# EEM_CONN.net
KiCad netlist of a schematic drawn in Altium Designer
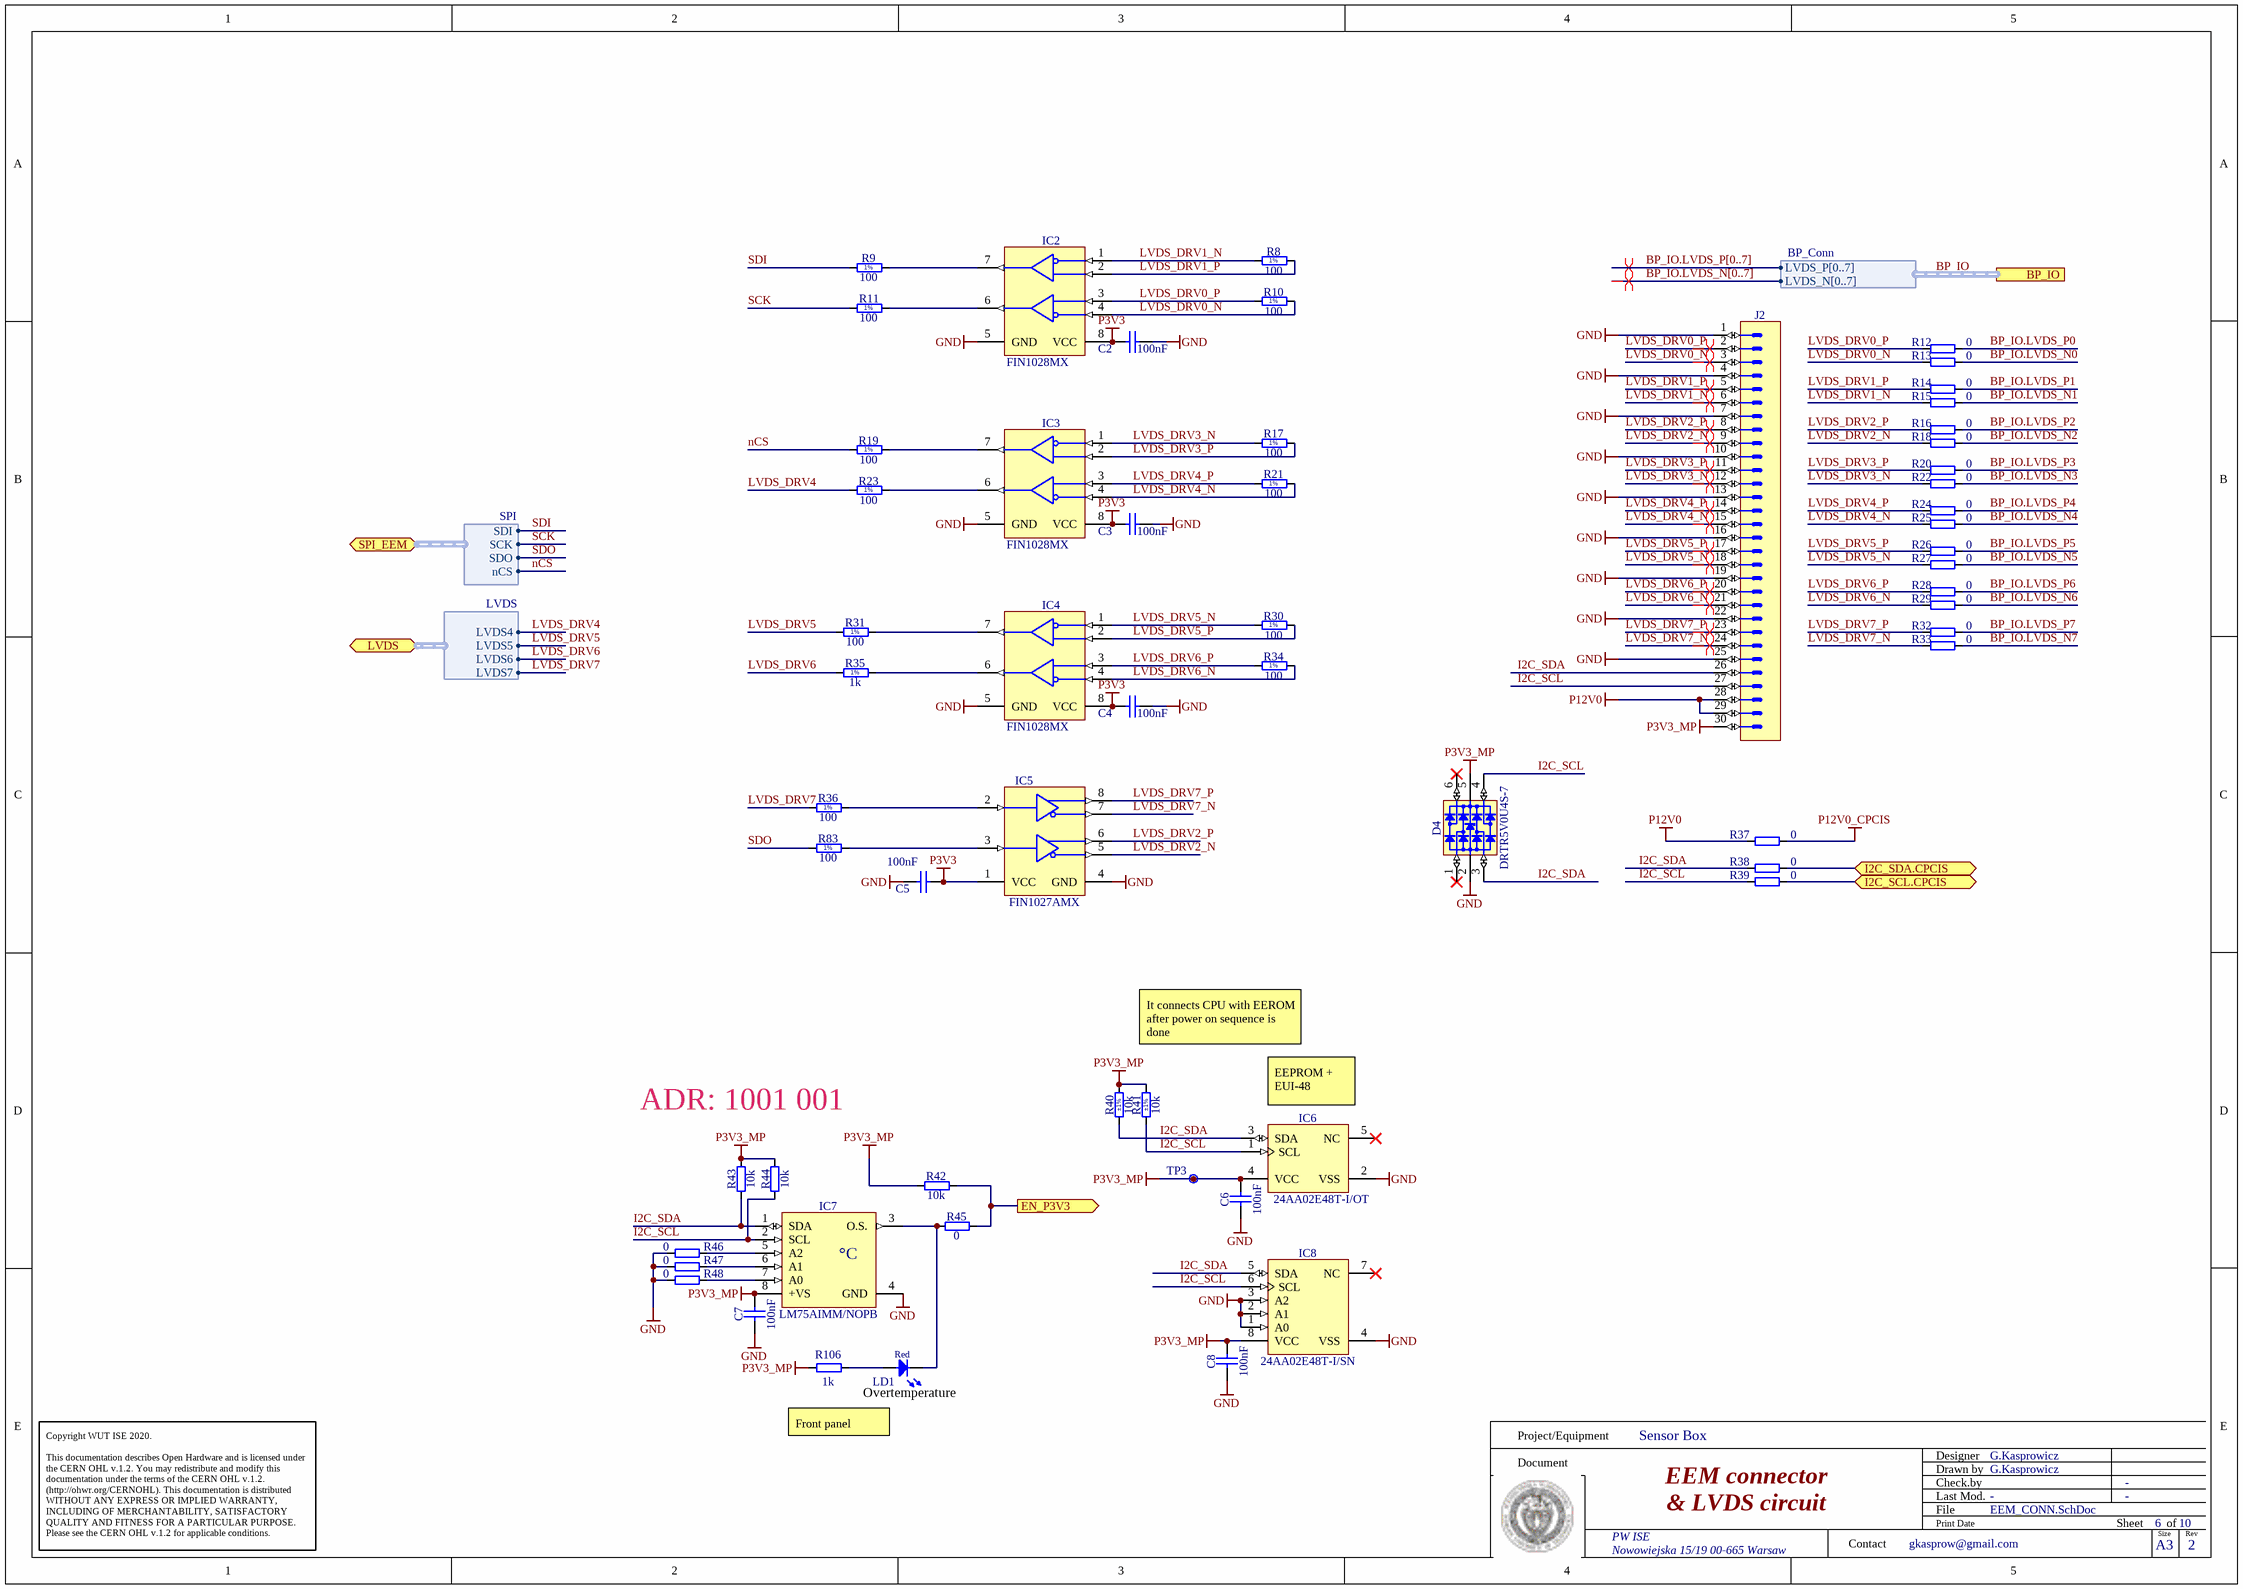
[diagram p0: EEM_CONN.SchDoc]

(export (version "E")
  (design (tool "Eeschema 10.0.6"))
  (components
    (comp (ref "C2")
      (value "100nF")
      (footprint "CAPC1005X55N")
      (description "Non-polarised capacitor")
      (fields
        (field (name "PART NUMBER") "CC0402_100NF_16V_10%_X5R")
        (field (name "VOLTAGE") "16V")
        (field (name "AUTHOR") "CERN DEM JLC")
      )
      (libsource (lib "Capacitors") (part "Capacitor - non polarized"))
    )
    (comp (ref "C3")
      (value "100nF")
      (footprint "CAPC1005X55N")
      (description "Non-polarised capacitor")
      (fields
        (field (name "PART NUMBER") "CC0402_100NF_16V_10%_X5R")
        (field (name "VOLTAGE") "16V")
        (field (name "AUTHOR") "CERN DEM JLC")
      )
      (libsource (lib "Capacitors") (part "Capacitor - non polarized"))
    )
    (comp (ref "C4")
      (value "100nF")
      (footprint "CAPC1005X55N")
      (description "Non-polarised capacitor")
      (fields
        (field (name "PART NUMBER") "CC0402_100NF_16V_10%_X5R")
        (field (name "VOLTAGE") "16V")
        (field (name "AUTHOR") "CERN DEM JLC")
      )
      (libsource (lib "Capacitors") (part "Capacitor - non polarized"))
    )
    (comp (ref "C5")
      (value "100nF")
      (footprint "CAPC1005X55N")
      (description "Non-polarised capacitor")
      (fields
        (field (name "PART NUMBER") "CC0402_100NF_16V_10%_X5R")
        (field (name "VOLTAGE") "16V")
        (field (name "AUTHOR") "CERN DEM JLC")
      )
      (libsource (lib "Capacitors") (part "Capacitor - non polarized"))
    )
    (comp (ref "C6")
      (value "100nF")
      (footprint "CAPC1005X55N")
      (description "Non-polarised capacitor")
      (fields
        (field (name "PART NUMBER") "CC0402_100NF_16V_10%_X5R")
        (field (name "VOLTAGE") "16V")
        (field (name "AUTHOR") "CERN DEM JLC")
      )
      (libsource (lib "Capacitors") (part "Capacitor - non polarized"))
    )
    (comp (ref "C7")
      (value "100nF")
      (footprint "CAPC1005X55N")
      (description "Non-polarised capacitor")
      (fields
        (field (name "PART NUMBER") "CC0402_100NF_16V_10%_X5R")
        (field (name "VOLTAGE") "16V")
        (field (name "AUTHOR") "CERN DEM JLC")
      )
      (libsource (lib "Capacitors") (part "Capacitor - non polarized"))
    )
    (comp (ref "C8")
      (value "100nF")
      (footprint "CAPC1005X55N")
      (description "Non-polarised capacitor")
      (fields
        (field (name "PART NUMBER") "CC0402_100NF_16V_10%_X5R")
        (field (name "VOLTAGE") "16V")
        (field (name "AUTHOR") "CERN DEM JLC")
      )
      (libsource (lib "Capacitors") (part "Capacitor - non polarized"))
    )
    (comp (ref "D4")
      (value "DRTR5V0U4S-7")
      (footprint "SOT65P210X110-6N")
      (description "Integrated Quad Ultra-Low Capacitance ESD Protection")
      (fields (field (name "MANUFACTURER") "DIODES") (field (name "AUTHOR") "GK"))
      (libsource (lib "Diodes") (part "D_TVS_DRTR5V0U4S-7"))
    )
    (comp (ref "IC2")
      (value "FIN1028MX")
      (footprint "SOIC127P600X175-8N")
      (description "3.3V LVDS 2-Bit High-Speed Differential Reciever")
      (fields (field (name "MANUFACTURER") "ON Semiconductor") (field (name "AUTHOR") "GK"))
      (libsource (lib "LIBRARY_SCH") (part "IFC_FIN1028"))
    )
    (comp (ref "IC3")
      (value "FIN1028MX")
      (footprint "SOIC127P600X175-8N")
      (description "3.3V LVDS 2-Bit High-Speed Differential Reciever")
      (fields (field (name "MANUFACTURER") "ON Semiconductor") (field (name "AUTHOR") "GK"))
      (libsource (lib "LIBRARY_SCH") (part "IFC_FIN1028"))
    )
    (comp (ref "IC4")
      (value "FIN1028MX")
      (footprint "SOIC127P600X175-8N")
      (description "3.3V LVDS 2-Bit High-Speed Differential Reciever")
      (fields (field (name "MANUFACTURER") "ON Semiconductor") (field (name "AUTHOR") "GK"))
      (libsource (lib "LIBRARY_SCH") (part "IFC_FIN1028"))
    )
    (comp (ref "IC5")
      (value "FIN1027AMX")
      (footprint "SOIC127P600X175-8N")
      (description "3.3V LVDS, 2-Bit, High-Speed, Differential Driver")
      (fields (field (name "MANUFACTURER") "ON Semiconductor") (field (name "AUTHOR") "GK"))
      (libsource (lib "LIBRARY_SCH") (part "IFC_FIN1027A"))
    )
    (comp (ref "IC6")
      (value "24AA02E48T-I/OT")
      (footprint "SOT95P280X145-5N")
      (description "1.7V-5.5V, 2K I2C Serial EEPROM With EUI-48 Node Identity")
      (fields (field (name "MANUFACTURER") "MICROCHIP TECHNOLOGY") (field (name "AUTHOR") "CERN DEM MR"))
      (libsource (lib "ICs And Semiconductors") (part "24AA02E48T-I/OT"))
    )
    (comp (ref "IC7")
      (value "LM75AIMM/NOPB")
      (footprint "SOP65P490X109-8N")
      (description "Digital Temperature Sensor and Thermal Watchdog with Two-Wire Interface")
      (fields (field (name "MANUFACTURER") "TEXAS INSTRUMENTS") (field (name "AUTHOR") "CERN DEM JLC"))
      (libsource (lib "ICs And Semiconductors") (part "LM75"))
    )
    (comp (ref "IC8")
      (value "24AA02E48T-I/SN")
      (footprint "SOIC127P600X175-8N")
      (description "1.7V-5.5V, 2K I2C™ Serial EEPROMs with EUI-48™ Node Identity")
      (fields (field (name "MANUFACTURER") "MICROCHIP TECHNOLOGY") (field (name "AUTHOR") "CERN DEM MR"))
      (libsource (lib "ICs And Semiconductors") (part "24AA025E48-I/SN"))
    )
    (comp (ref "J2")
      (value "IDC")
      (footprint "3M_N2530-6002RB")
      (description "Connector 30 Male")
      (fields
        (field (name "PART NUMBER") "3M_N2530-6002RB")
        (field (name "MANUFACTURER") "3M")
        (field (name "AUTHOR") "CERN DEM JLC")
      )
      (libsource (lib "Connectors") (part "Connector 30 Male"))
    )
    (comp (ref "LD1")
      (value "Red")
      (footprint "LED_DIALIGHT_555-200")
      (description "LED Red 1C 2A")
      (fields
        (field (name "PART NUMBER") "LED_DIALIGHT_555-2001F")
        (field (name "MANUFACTURER") "DIALIGHT")
        (field (name "AUTHOR") "CERN DEM JMW")
      )
      (libsource (lib "ICs And Semiconductors") (part "LED Red 1C 2A"))
    )
    (comp (ref "R8")
      (value "100")
      (footprint "RESC1005X40N")
      (description "Resistor - 1%")
      (fields
        (field (name "PART NUMBER") "R0402_100R_1%_0.0625W_100PPM")
        (field (name "POWER") "0.0625W")
        (field (name "AUTHOR") "CERN DEM JLC")
      )
      (libsource (lib "Resistors") (part "Resistor - 1%"))
    )
    (comp (ref "R9")
      (value "100")
      (footprint "RESC1005X40N")
      (description "Resistor - 1%")
      (fields
        (field (name "PART NUMBER") "R0402_100R_1%_0.0625W_100PPM")
        (field (name "POWER") "0.0625W")
        (field (name "AUTHOR") "CERN DEM JLC")
      )
      (libsource (lib "Resistors") (part "Resistor - 1%"))
    )
    (comp (ref "R10")
      (value "100")
      (footprint "RESC1005X40N")
      (description "Resistor - 1%")
      (fields
        (field (name "PART NUMBER") "R0402_100R_1%_0.0625W_100PPM")
        (field (name "POWER") "0.0625W")
        (field (name "AUTHOR") "CERN DEM JLC")
      )
      (libsource (lib "Resistors") (part "Resistor - 1%"))
    )
    (comp (ref "R11")
      (value "100")
      (footprint "RESC1005X40N")
      (description "Resistor - 1%")
      (fields
        (field (name "PART NUMBER") "R0402_100R_1%_0.0625W_100PPM")
        (field (name "POWER") "0.0625W")
        (field (name "AUTHOR") "CERN DEM JLC")
      )
      (libsource (lib "Resistors") (part "Resistor - 1%"))
    )
    (comp (ref "R12")
      (value "0")
      (footprint "RESC1005X40N")
      (description "Resistor")
      (fields
        (field (name "PART NUMBER") "R0402_0R_JUMPER")
        (field (name "MANUFACTURER") "GENERIC")
        (field (name "AUTHOR") "CERN DEM JLC")
      )
      (libsource (lib "Resistors") (part "Resistor"))
    )
    (comp (ref "R13")
      (value "0")
      (footprint "RESC1005X40N")
      (description "Resistor")
      (fields
        (field (name "PART NUMBER") "R0402_0R_JUMPER")
        (field (name "MANUFACTURER") "GENERIC")
        (field (name "AUTHOR") "CERN DEM JLC")
      )
      (libsource (lib "Resistors") (part "Resistor"))
    )
    (comp (ref "R14")
      (value "0")
      (footprint "RESC1005X40N")
      (description "Resistor")
      (fields
        (field (name "PART NUMBER") "R0402_0R_JUMPER")
        (field (name "MANUFACTURER") "GENERIC")
        (field (name "AUTHOR") "CERN DEM JLC")
      )
      (libsource (lib "Resistors") (part "Resistor"))
    )
    (comp (ref "R15")
      (value "0")
      (footprint "RESC1005X40N")
      (description "Resistor")
      (fields
        (field (name "PART NUMBER") "R0402_0R_JUMPER")
        (field (name "MANUFACTURER") "GENERIC")
        (field (name "AUTHOR") "CERN DEM JLC")
      )
      (libsource (lib "Resistors") (part "Resistor"))
    )
    (comp (ref "R16")
      (value "0")
      (footprint "RESC1005X40N")
      (description "Resistor")
      (fields
        (field (name "PART NUMBER") "R0402_0R_JUMPER")
        (field (name "MANUFACTURER") "GENERIC")
        (field (name "AUTHOR") "CERN DEM JLC")
      )
      (libsource (lib "Resistors") (part "Resistor"))
    )
    (comp (ref "R17")
      (value "100")
      (footprint "RESC1005X40N")
      (description "Resistor - 1%")
      (fields
        (field (name "PART NUMBER") "R0402_100R_1%_0.0625W_100PPM")
        (field (name "POWER") "0.0625W")
        (field (name "AUTHOR") "CERN DEM JLC")
      )
      (libsource (lib "Resistors") (part "Resistor - 1%"))
    )
    (comp (ref "R18")
      (value "0")
      (footprint "RESC1005X40N")
      (description "Resistor")
      (fields
        (field (name "PART NUMBER") "R0402_0R_JUMPER")
        (field (name "MANUFACTURER") "GENERIC")
        (field (name "AUTHOR") "CERN DEM JLC")
      )
      (libsource (lib "Resistors") (part "Resistor"))
    )
    (comp (ref "R19")
      (value "100")
      (footprint "RESC1005X40N")
      (description "Resistor - 1%")
      (fields
        (field (name "PART NUMBER") "R0402_100R_1%_0.0625W_100PPM")
        (field (name "POWER") "0.0625W")
        (field (name "AUTHOR") "CERN DEM JLC")
      )
      (libsource (lib "Resistors") (part "Resistor - 1%"))
    )
    (comp (ref "R20")
      (value "0")
      (footprint "RESC1005X40N")
      (description "Resistor")
      (fields
        (field (name "PART NUMBER") "R0402_0R_JUMPER")
        (field (name "MANUFACTURER") "GENERIC")
        (field (name "AUTHOR") "CERN DEM JLC")
      )
      (libsource (lib "Resistors") (part "Resistor"))
    )
    (comp (ref "R21")
      (value "100")
      (footprint "RESC1005X40N")
      (description "Resistor - 1%")
      (fields
        (field (name "PART NUMBER") "R0402_100R_1%_0.0625W_100PPM")
        (field (name "POWER") "0.0625W")
        (field (name "AUTHOR") "CERN DEM JLC")
      )
      (libsource (lib "Resistors") (part "Resistor - 1%"))
    )
    (comp (ref "R22")
      (value "0")
      (footprint "RESC1005X40N")
      (description "Resistor")
      (fields
        (field (name "PART NUMBER") "R0402_0R_JUMPER")
        (field (name "MANUFACTURER") "GENERIC")
        (field (name "AUTHOR") "CERN DEM JLC")
      )
      (libsource (lib "Resistors") (part "Resistor"))
    )
    (comp (ref "R23")
      (value "100")
      (footprint "RESC1005X40N")
      (description "Resistor - 1%")
      (fields
        (field (name "PART NUMBER") "R0402_100R_1%_0.0625W_100PPM")
        (field (name "POWER") "0.0625W")
        (field (name "AUTHOR") "CERN DEM JLC")
      )
      (libsource (lib "Resistors") (part "Resistor - 1%"))
    )
    (comp (ref "R24")
      (value "0")
      (footprint "RESC1005X40N")
      (description "Resistor")
      (fields
        (field (name "PART NUMBER") "R0402_0R_JUMPER")
        (field (name "MANUFACTURER") "GENERIC")
        (field (name "AUTHOR") "CERN DEM JLC")
      )
      (libsource (lib "Resistors") (part "Resistor"))
    )
    (comp (ref "R25")
      (value "0")
      (footprint "RESC1005X40N")
      (description "Resistor")
      (fields
        (field (name "PART NUMBER") "R0402_0R_JUMPER")
        (field (name "MANUFACTURER") "GENERIC")
        (field (name "AUTHOR") "CERN DEM JLC")
      )
      (libsource (lib "Resistors") (part "Resistor"))
    )
    (comp (ref "R26")
      (value "0")
      (footprint "RESC1005X40N")
      (description "Resistor")
      (fields
        (field (name "PART NUMBER") "R0402_0R_JUMPER")
        (field (name "MANUFACTURER") "GENERIC")
        (field (name "AUTHOR") "CERN DEM JLC")
      )
      (libsource (lib "Resistors") (part "Resistor"))
    )
    (comp (ref "R27")
      (value "0")
      (footprint "RESC1005X40N")
      (description "Resistor")
      (fields
        (field (name "PART NUMBER") "R0402_0R_JUMPER")
        (field (name "MANUFACTURER") "GENERIC")
        (field (name "AUTHOR") "CERN DEM JLC")
      )
      (libsource (lib "Resistors") (part "Resistor"))
    )
    (comp (ref "R28")
      (value "0")
      (footprint "RESC1005X40N")
      (description "Resistor")
      (fields
        (field (name "PART NUMBER") "R0402_0R_JUMPER")
        (field (name "MANUFACTURER") "GENERIC")
        (field (name "AUTHOR") "CERN DEM JLC")
      )
      (libsource (lib "Resistors") (part "Resistor"))
    )
    (comp (ref "R29")
      (value "0")
      (footprint "RESC1005X40N")
      (description "Resistor")
      (fields
        (field (name "PART NUMBER") "R0402_0R_JUMPER")
        (field (name "MANUFACTURER") "GENERIC")
        (field (name "AUTHOR") "CERN DEM JLC")
      )
      (libsource (lib "Resistors") (part "Resistor"))
    )
    (comp (ref "R30")
      (value "100")
      (footprint "RESC1005X40N")
      (description "Resistor - 1%")
      (fields
        (field (name "PART NUMBER") "R0402_100R_1%_0.0625W_100PPM")
        (field (name "POWER") "0.0625W")
        (field (name "AUTHOR") "CERN DEM JLC")
      )
      (libsource (lib "Resistors") (part "Resistor - 1%"))
    )
    (comp (ref "R31")
      (value "100")
      (footprint "RESC1005X40N")
      (description "Resistor - 1%")
      (fields
        (field (name "PART NUMBER") "R0402_100R_1%_0.0625W_100PPM")
        (field (name "POWER") "0.0625W")
        (field (name "AUTHOR") "CERN DEM JLC")
      )
      (libsource (lib "Resistors") (part "Resistor - 1%"))
    )
    (comp (ref "R32")
      (value "0")
      (footprint "RESC1005X40N")
      (description "Resistor")
      (fields
        (field (name "PART NUMBER") "R0402_0R_JUMPER")
        (field (name "MANUFACTURER") "GENERIC")
        (field (name "AUTHOR") "CERN DEM JLC")
      )
      (libsource (lib "Resistors") (part "Resistor"))
    )
    (comp (ref "R33")
      (value "0")
      (footprint "RESC1005X40N")
      (description "Resistor")
      (fields
        (field (name "PART NUMBER") "R0402_0R_JUMPER")
        (field (name "MANUFACTURER") "GENERIC")
        (field (name "AUTHOR") "CERN DEM JLC")
      )
      (libsource (lib "Resistors") (part "Resistor"))
    )
    (comp (ref "R34")
      (value "100")
      (footprint "RESC1005X40N")
      (description "Resistor - 1%")
      (fields
        (field (name "PART NUMBER") "R0402_100R_1%_0.0625W_100PPM")
        (field (name "POWER") "0.0625W")
        (field (name "AUTHOR") "CERN DEM JLC")
      )
      (libsource (lib "Resistors") (part "Resistor - 1%"))
    )
    (comp (ref "R35")
      (value "1k")
      (footprint "RESC1005X40N")
      (description "Resistor - 1%")
      (fields
        (field (name "PART NUMBER") "R0402_1K_1%_0.0625W_100PPM")
        (field (name "POWER") "0.0625W")
        (field (name "AUTHOR") "CERN DEM JLC")
      )
      (libsource (lib "Resistors") (part "Resistor - 1%"))
    )
    (comp (ref "R36")
      (value "100")
      (footprint "RESC1005X40N")
      (description "Resistor - 1%")
      (fields
        (field (name "PART NUMBER") "R0402_100R_1%_0.0625W_100PPM")
        (field (name "POWER") "0.0625W")
        (field (name "AUTHOR") "CERN DEM JLC")
      )
      (libsource (lib "Resistors") (part "Resistor - 1%"))
    )
    (comp (ref "R37")
      (value "0")
      (footprint "RESC2012X60N")
      (description "Resistor")
      (fields
        (field (name "PART NUMBER") "R0805_0R_JUMPER")
        (field (name "MANUFACTURER") "GENERIC")
        (field (name "AUTHOR") "CERN DEM JLC")
      )
      (libsource (lib "Resistors") (part "Resistor"))
    )
    (comp (ref "R38")
      (value "0")
      (footprint "RESC1005X40N")
      (description "Resistor")
      (fields
        (field (name "PART NUMBER") "R0402_0R_JUMPER")
        (field (name "MANUFACTURER") "GENERIC")
        (field (name "AUTHOR") "CERN DEM JLC")
      )
      (libsource (lib "Resistors") (part "Resistor"))
    )
    (comp (ref "R39")
      (value "0")
      (footprint "RESC1005X40N")
      (description "Resistor")
      (fields
        (field (name "PART NUMBER") "R0402_0R_JUMPER")
        (field (name "MANUFACTURER") "GENERIC")
        (field (name "AUTHOR") "CERN DEM JLC")
      )
      (libsource (lib "Resistors") (part "Resistor"))
    )
    (comp (ref "R40")
      (value "10k")
      (footprint "RESC1005X40N")
      (description "Resistor - 1%")
      (fields
        (field (name "TOLERANCE") "±1%")
        (field (name "PART NUMBER") "R0402_10K_1%_0.0625W_100PPM")
        (field (name "POWER") "0.0625W")
        (field (name "AUTHOR") "CERN DEM JLC")
      )
      (libsource (lib "Resistors") (part "Resistor - 1%"))
    )
    (comp (ref "R41")
      (value "10k")
      (footprint "RESC1005X40N")
      (description "Resistor - 1%")
      (fields
        (field (name "TOLERANCE") "±1%")
        (field (name "PART NUMBER") "R0402_10K_1%_0.0625W_100PPM")
        (field (name "POWER") "0.0625W")
        (field (name "AUTHOR") "CERN DEM JLC")
      )
      (libsource (lib "Resistors") (part "Resistor - 1%"))
    )
    (comp (ref "R42")
      (value "10k")
      (footprint "RESC1005X40N")
      (description "Resistor - 1%")
      (fields
        (field (name "PART NUMBER") "R0402_10K_1%_0.0625W_100PPM")
        (field (name "POWER") "0.0625W")
        (field (name "AUTHOR") "CERN DEM JLC")
      )
      (libsource (lib "Resistors") (part "Resistor - 1%"))
    )
    (comp (ref "R43")
      (value "10k")
      (footprint "RESC1005X40N")
      (description "Resistor - 1%")
      (fields
        (field (name "PART NUMBER") "R0402_10K_1%_0.0625W_100PPM")
        (field (name "POWER") "0.0625W")
        (field (name "AUTHOR") "CERN DEM JLC")
      )
      (libsource (lib "Resistors") (part "Resistor - 1%"))
    )
    (comp (ref "R44")
      (value "10k")
      (footprint "RESC1005X40N")
      (description "Resistor - 1%")
      (fields
        (field (name "PART NUMBER") "R0402_10K_1%_0.0625W_100PPM")
        (field (name "POWER") "0.0625W")
        (field (name "AUTHOR") "CERN DEM JLC")
      )
      (libsource (lib "Resistors") (part "Resistor - 1%"))
    )
    (comp (ref "R45")
      (value "0")
      (footprint "RESC1005X40N")
      (description "Resistor")
      (fields
        (field (name "PART NUMBER") "R0402_0R_JUMPER")
        (field (name "MANUFACTURER") "GENERIC")
        (field (name "AUTHOR") "CERN DEM JLC")
      )
      (libsource (lib "Resistors") (part "Resistor"))
    )
    (comp (ref "R46")
      (value "0")
      (footprint "RESC1005X40N")
      (description "Resistor")
      (fields
        (field (name "PART NUMBER") "R0402_0R_JUMPER")
        (field (name "MANUFACTURER") "GENERIC")
        (field (name "AUTHOR") "CERN DEM JLC")
      )
      (libsource (lib "Resistors") (part "Resistor"))
    )
    (comp (ref "R47")
      (value "0")
      (footprint "RESC1005X40N")
      (description "Resistor")
      (fields
        (field (name "PART NUMBER") "R0402_0R_JUMPER")
        (field (name "MANUFACTURER") "GENERIC")
        (field (name "AUTHOR") "CERN DEM JLC")
      )
      (libsource (lib "Resistors") (part "Resistor"))
    )
    (comp (ref "R48")
      (value "0")
      (footprint "RESC1005X40N")
      (description "Resistor")
      (fields
        (field (name "PART NUMBER") "R0402_0R_JUMPER")
        (field (name "MANUFACTURER") "GENERIC")
        (field (name "AUTHOR") "CERN DEM JLC")
      )
      (libsource (lib "Resistors") (part "Resistor"))
    )
    (comp (ref "R83")
      (value "100")
      (footprint "RESC1005X40N")
      (description "Resistor - 1%")
      (fields
        (field (name "PART NUMBER") "R0402_100R_1%_0.0625W_100PPM")
        (field (name "POWER") "0.0625W")
        (field (name "AUTHOR") "CERN DEM JLC")
      )
      (libsource (lib "Resistors") (part "Resistor - 1%"))
    )
    (comp (ref "R106")
      (value "1k")
      (footprint "RESC1005X40N")
      (description "Resistor - 1%")
      (fields
        (field (name "PART NUMBER") "R0402_1K_1%_0.0625W_100PPM")
        (field (name "POWER") "0.0625W")
        (field (name "AUTHOR") "CERN DEM JLC")
      )
      (libsource (lib "Resistors") (part "Resistor - 1%"))
    )
    (comp (ref "TP3")
      (value "Test Point")
      (footprint "TPS127")
      (fields (field (name "PART NUMBER") "SMD_PAD_1.27X1.27MM") (field (name "AUTHOR") "CERN DEM JLC"))
      (libsource (lib "Eletro-mechanical") (part "Test Point"))
    )
  )
  (nets
    (net (code "4") (name "/BP_IO.LVDS_N0") (class "Default")
      (node (ref "R13") (pin "2") (pinfunction "2_2") (pintype "passive"))
    )
    (net (code "5") (name "/BP_IO.LVDS_N1") (class "Default")
      (node (ref "R15") (pin "2") (pinfunction "2_2") (pintype "passive"))
    )
    (net (code "6") (name "/BP_IO.LVDS_N2") (class "Default")
      (node (ref "R18") (pin "2") (pinfunction "2_2") (pintype "passive"))
    )
    (net (code "7") (name "/BP_IO.LVDS_N3") (class "Default")
      (node (ref "R22") (pin "2") (pinfunction "2_2") (pintype "passive"))
    )
    (net (code "8") (name "/BP_IO.LVDS_N4") (class "Default")
      (node (ref "R25") (pin "2") (pinfunction "2_2") (pintype "passive"))
    )
    (net (code "9") (name "/BP_IO.LVDS_N5") (class "Default")
      (node (ref "R27") (pin "2") (pinfunction "2_2") (pintype "passive"))
    )
    (net (code "10") (name "/BP_IO.LVDS_N6") (class "Default")
      (node (ref "R29") (pin "2") (pinfunction "2_2") (pintype "passive"))
    )
    (net (code "11") (name "/BP_IO.LVDS_N7") (class "Default")
      (node (ref "R33") (pin "2") (pinfunction "2_2") (pintype "passive"))
    )
    (net (code "13") (name "/BP_IO.LVDS_P0") (class "Default")
      (node (ref "R12") (pin "2") (pinfunction "2_2") (pintype "passive"))
    )
    (net (code "14") (name "/BP_IO.LVDS_P1") (class "Default")
      (node (ref "R14") (pin "2") (pinfunction "2_2") (pintype "passive"))
    )
    (net (code "15") (name "/BP_IO.LVDS_P2") (class "Default")
      (node (ref "R16") (pin "2") (pinfunction "2_2") (pintype "passive"))
    )
    (net (code "16") (name "/BP_IO.LVDS_P3") (class "Default")
      (node (ref "R20") (pin "2") (pinfunction "2_2") (pintype "passive"))
    )
    (net (code "17") (name "/BP_IO.LVDS_P4") (class "Default")
      (node (ref "R24") (pin "2") (pinfunction "2_2") (pintype "passive"))
    )
    (net (code "18") (name "/BP_IO.LVDS_P5") (class "Default")
      (node (ref "R26") (pin "2") (pinfunction "2_2") (pintype "passive"))
    )
    (net (code "19") (name "/BP_IO.LVDS_P6") (class "Default")
      (node (ref "R28") (pin "2") (pinfunction "2_2") (pintype "passive"))
    )
    (net (code "20") (name "/BP_IO.LVDS_P7") (class "Default")
      (node (ref "R32") (pin "2") (pinfunction "2_2") (pintype "passive"))
    )
    (net (code "23") (name "/EN_P3V3") (class "Default")
      (node (ref "R42") (pin "2") (pinfunction "2_2") (pintype "passive"))
      (node (ref "R45") (pin "2") (pinfunction "2_2") (pintype "passive"))
    )
    (net (code "24") (name "/I2C_SCL") (class "Default")
      (node (ref "D4") (pin "4") (pinfunction "I/O3_4") (pintype "bidirectional"))
      (node (ref "IC6") (pin "1") (pinfunction "SCL_1") (pintype "input"))
      (node (ref "IC7") (pin "2") (pinfunction "SCL_2") (pintype "input"))
      (node (ref "IC8") (pin "6") (pinfunction "SCL_6") (pintype "input"))
      (node (ref "J2") (pin "27") (pinfunction "27_27") (pintype "bidirectional"))
      (node (ref "R39") (pin "1") (pinfunction "1_1") (pintype "passive"))
      (node (ref "R41") (pin "1") (pinfunction "1_1") (pintype "passive"))
      (node (ref "R44") (pin "1") (pinfunction "1_1") (pintype "passive"))
    )
    (net (code "25") (name "/I2C_SCL.CPCIS") (class "Default")
      (node (ref "R39") (pin "2") (pinfunction "2_2") (pintype "passive"))
    )
    (net (code "26") (name "/I2C_SDA") (class "Default")
      (node (ref "D4") (pin "3") (pinfunction "I/O2_3") (pintype "bidirectional"))
      (node (ref "IC6") (pin "3") (pinfunction "SDA_3") (pintype "bidirectional"))
      (node (ref "IC7") (pin "1") (pinfunction "SDA_1") (pintype "bidirectional"))
      (node (ref "IC8") (pin "5") (pinfunction "SDA_5") (pintype "bidirectional"))
      (node (ref "J2") (pin "26") (pinfunction "26_26") (pintype "bidirectional"))
      (node (ref "R38") (pin "1") (pinfunction "1_1") (pintype "passive"))
      (node (ref "R40") (pin "1") (pinfunction "1_1") (pintype "passive"))
      (node (ref "R43") (pin "1") (pinfunction "1_1") (pintype "passive"))
    )
    (net (code "27") (name "/I2C_SDA.CPCIS") (class "Default")
      (node (ref "R38") (pin "2") (pinfunction "2_2") (pintype "passive"))
    )
    (net (code "28") (name "/LVDS_DRV0_N") (class "Default")
      (node (ref "IC2") (pin "4") (pinfunction "RIN2-_4") (pintype "input"))
      (node (ref "J2") (pin "3") (pinfunction "3_3") (pintype "bidirectional"))
      (node (ref "R10") (pin "2") (pinfunction "2_2") (pintype "passive"))
      (node (ref "R13") (pin "1") (pinfunction "1_1") (pintype "passive"))
    )
    (net (code "29") (name "/LVDS_DRV0_P") (class "Default")
      (node (ref "IC2") (pin "3") (pinfunction "RIN2+_3") (pintype "input"))
      (node (ref "J2") (pin "2") (pinfunction "2_2") (pintype "bidirectional"))
      (node (ref "R10") (pin "1") (pinfunction "1_1") (pintype "passive"))
      (node (ref "R12") (pin "1") (pinfunction "1_1") (pintype "passive"))
    )
    (net (code "30") (name "/LVDS_DRV1_N") (class "Default")
      (node (ref "IC2") (pin "1") (pinfunction "RIN1-_1") (pintype "input"))
      (node (ref "J2") (pin "6") (pinfunction "6_6") (pintype "bidirectional"))
      (node (ref "R15") (pin "1") (pinfunction "1_1") (pintype "passive"))
      (node (ref "R8") (pin "1") (pinfunction "1_1") (pintype "passive"))
    )
    (net (code "31") (name "/LVDS_DRV1_P") (class "Default")
      (node (ref "IC2") (pin "2") (pinfunction "RIN1+_2") (pintype "input"))
      (node (ref "J2") (pin "5") (pinfunction "5_5") (pintype "bidirectional"))
      (node (ref "R14") (pin "1") (pinfunction "1_1") (pintype "passive"))
      (node (ref "R8") (pin "2") (pinfunction "2_2") (pintype "passive"))
    )
    (net (code "32") (name "/LVDS_DRV2_N") (class "Default")
      (node (ref "IC5") (pin "5") (pinfunction "DOUT-_5") (pintype "output"))
      (node (ref "J2") (pin "9") (pinfunction "9_9") (pintype "bidirectional"))
      (node (ref "R18") (pin "1") (pinfunction "1_1") (pintype "passive"))
    )
    (net (code "33") (name "/LVDS_DRV2_P") (class "Default")
      (node (ref "IC5") (pin "6") (pinfunction "DOUT+_6") (pintype "output"))
      (node (ref "J2") (pin "8") (pinfunction "8_8") (pintype "bidirectional"))
      (node (ref "R16") (pin "1") (pinfunction "1_1") (pintype "passive"))
    )
    (net (code "34") (name "/LVDS_DRV3_N") (class "Default")
      (node (ref "IC3") (pin "1") (pinfunction "RIN1-_1") (pintype "input"))
      (node (ref "J2") (pin "12") (pinfunction "12_12") (pintype "bidirectional"))
      (node (ref "R17") (pin "1") (pinfunction "1_1") (pintype "passive"))
      (node (ref "R22") (pin "1") (pinfunction "1_1") (pintype "passive"))
    )
    (net (code "35") (name "/LVDS_DRV3_P") (class "Default")
      (node (ref "IC3") (pin "2") (pinfunction "RIN1+_2") (pintype "input"))
      (node (ref "J2") (pin "11") (pinfunction "11_11") (pintype "bidirectional"))
      (node (ref "R17") (pin "2") (pinfunction "2_2") (pintype "passive"))
      (node (ref "R20") (pin "1") (pinfunction "1_1") (pintype "passive"))
    )
    (net (code "36") (name "/LVDS_DRV4") (class "Default")
      (node (ref "R23") (pin "1") (pinfunction "1_1") (pintype "passive"))
    )
    (net (code "37") (name "/LVDS_DRV4_N") (class "Default")
      (node (ref "IC3") (pin "4") (pinfunction "RIN2-_4") (pintype "input"))
      (node (ref "J2") (pin "15") (pinfunction "15_15") (pintype "bidirectional"))
      (node (ref "R21") (pin "2") (pinfunction "2_2") (pintype "passive"))
      (node (ref "R25") (pin "1") (pinfunction "1_1") (pintype "passive"))
    )
    (net (code "38") (name "/LVDS_DRV4_P") (class "Default")
      (node (ref "IC3") (pin "3") (pinfunction "RIN2+_3") (pintype "input"))
      (node (ref "J2") (pin "14") (pinfunction "14_14") (pintype "bidirectional"))
      (node (ref "R21") (pin "1") (pinfunction "1_1") (pintype "passive"))
      (node (ref "R24") (pin "1") (pinfunction "1_1") (pintype "passive"))
    )
    (net (code "39") (name "/LVDS_DRV5") (class "Default")
      (node (ref "R31") (pin "1") (pinfunction "1_1") (pintype "passive"))
    )
    (net (code "40") (name "/LVDS_DRV5_N") (class "Default")
      (node (ref "IC4") (pin "1") (pinfunction "RIN1-_1") (pintype "input"))
      (node (ref "J2") (pin "18") (pinfunction "18_18") (pintype "bidirectional"))
      (node (ref "R27") (pin "1") (pinfunction "1_1") (pintype "passive"))
      (node (ref "R30") (pin "1") (pinfunction "1_1") (pintype "passive"))
    )
    (net (code "41") (name "/LVDS_DRV5_P") (class "Default")
      (node (ref "IC4") (pin "2") (pinfunction "RIN1+_2") (pintype "input"))
      (node (ref "J2") (pin "17") (pinfunction "17_17") (pintype "bidirectional"))
      (node (ref "R26") (pin "1") (pinfunction "1_1") (pintype "passive"))
      (node (ref "R30") (pin "2") (pinfunction "2_2") (pintype "passive"))
    )
    (net (code "42") (name "/LVDS_DRV6") (class "Default")
      (node (ref "R35") (pin "1") (pinfunction "1_1") (pintype "passive"))
    )
    (net (code "43") (name "/LVDS_DRV6_N") (class "Default")
      (node (ref "IC4") (pin "4") (pinfunction "RIN2-_4") (pintype "input"))
      (node (ref "J2") (pin "21") (pinfunction "21_21") (pintype "bidirectional"))
      (node (ref "R29") (pin "1") (pinfunction "1_1") (pintype "passive"))
      (node (ref "R34") (pin "2") (pinfunction "2_2") (pintype "passive"))
    )
    (net (code "44") (name "/LVDS_DRV6_P") (class "Default")
      (node (ref "IC4") (pin "3") (pinfunction "RIN2+_3") (pintype "input"))
      (node (ref "J2") (pin "20") (pinfunction "20_20") (pintype "bidirectional"))
      (node (ref "R28") (pin "1") (pinfunction "1_1") (pintype "passive"))
      (node (ref "R34") (pin "1") (pinfunction "1_1") (pintype "passive"))
    )
    (net (code "45") (name "/LVDS_DRV7") (class "Default")
      (node (ref "R36") (pin "1") (pinfunction "1_1") (pintype "passive"))
    )
    (net (code "46") (name "/LVDS_DRV7_N") (class "Default")
      (node (ref "IC5") (pin "7") (pinfunction "DOUT-_7") (pintype "output"))
      (node (ref "J2") (pin "24") (pinfunction "24_24") (pintype "bidirectional"))
      (node (ref "R33") (pin "1") (pinfunction "1_1") (pintype "passive"))
    )
    (net (code "47") (name "/LVDS_DRV7_P") (class "Default")
      (node (ref "IC5") (pin "8") (pinfunction "DOUT+_8") (pintype "output"))
      (node (ref "J2") (pin "23") (pinfunction "23_23") (pintype "bidirectional"))
      (node (ref "R32") (pin "1") (pinfunction "1_1") (pintype "passive"))
    )
    (net (code "48") (name "/SCK") (class "Default")
      (node (ref "R11") (pin "1") (pinfunction "1_1") (pintype "passive"))
    )
    (net (code "49") (name "/SDI") (class "Default")
      (node (ref "R9") (pin "1") (pinfunction "1_1") (pintype "passive"))
    )
    (net (code "50") (name "/SDO") (class "Default")
      (node (ref "R83") (pin "1") (pinfunction "1_1") (pintype "passive"))
    )
    (net (code "51") (name "/nCS") (class "Default")
      (node (ref "R19") (pin "1") (pinfunction "1_1") (pintype "passive"))
    )
    (net (code "54") (name "GND") (class "Default")
      (node (ref "C2") (pin "1") (pinfunction "1_1") (pintype "passive"))
      (node (ref "C3") (pin "1") (pinfunction "1_1") (pintype "passive"))
      (node (ref "C4") (pin "1") (pinfunction "1_1") (pintype "passive"))
      (node (ref "C5") (pin "1") (pinfunction "1_1") (pintype "passive"))
      (node (ref "C6") (pin "1") (pinfunction "1_1") (pintype "passive"))
      (node (ref "C7") (pin "1") (pinfunction "1_1") (pintype "passive"))
      (node (ref "C8") (pin "1") (pinfunction "1_1") (pintype "passive"))
      (node (ref "D4") (pin "2") (pinfunction "GND_2") (pintype "power_in"))
      (node (ref "IC2") (pin "5") (pinfunction "GND_5") (pintype "power_in"))
      (node (ref "IC3") (pin "5") (pinfunction "GND_5") (pintype "power_in"))
      (node (ref "IC4") (pin "5") (pinfunction "GND_5") (pintype "power_in"))
      (node (ref "IC5") (pin "4") (pinfunction "GND_4") (pintype "power_in"))
      (node (ref "IC6") (pin "2") (pinfunction "VSS_2") (pintype "power_in"))
      (node (ref "IC7") (pin "4") (pinfunction "GND_4") (pintype "power_in"))
      (node (ref "IC8") (pin "1") (pinfunction "A0_1") (pintype "input"))
      (node (ref "IC8") (pin "2") (pinfunction "A1_2") (pintype "input"))
      (node (ref "IC8") (pin "3") (pinfunction "A2_3") (pintype "input"))
      (node (ref "IC8") (pin "4") (pinfunction "VSS_4") (pintype "power_in"))
      (node (ref "J2") (pin "1") (pinfunction "1_1") (pintype "bidirectional"))
      (node (ref "J2") (pin "10") (pinfunction "10_10") (pintype "bidirectional"))
      (node (ref "J2") (pin "13") (pinfunction "13_13") (pintype "bidirectional"))
      (node (ref "J2") (pin "16") (pinfunction "16_16") (pintype "bidirectional"))
      (node (ref "J2") (pin "19") (pinfunction "19_19") (pintype "bidirectional"))
      (node (ref "J2") (pin "22") (pinfunction "22_22") (pintype "bidirectional"))
      (node (ref "J2") (pin "25") (pinfunction "25_25") (pintype "bidirectional"))
      (node (ref "J2") (pin "4") (pinfunction "4_4") (pintype "bidirectional"))
      (node (ref "J2") (pin "7") (pinfunction "7_7") (pintype "bidirectional"))
      (node (ref "R46") (pin "1") (pinfunction "1_1") (pintype "passive"))
      (node (ref "R47") (pin "1") (pinfunction "1_1") (pintype "passive"))
      (node (ref "R48") (pin "1") (pinfunction "1_1") (pintype "passive"))
    )
    (net (code "55") (name "Net-(IC2-ROUT1)") (class "Default")
      (node (ref "IC2") (pin "7") (pinfunction "ROUT1_7") (pintype "output"))
      (node (ref "R9") (pin "2") (pinfunction "2_2") (pintype "passive"))
    )
    (net (code "56") (name "Net-(IC2-ROUT2)") (class "Default")
      (node (ref "IC2") (pin "6") (pinfunction "ROUT2_6") (pintype "output"))
      (node (ref "R11") (pin "2") (pinfunction "2_2") (pintype "passive"))
    )
    (net (code "57") (name "Net-(IC3-ROUT1)") (class "Default")
      (node (ref "IC3") (pin "7") (pinfunction "ROUT1_7") (pintype "output"))
      (node (ref "R19") (pin "2") (pinfunction "2_2") (pintype "passive"))
    )
    (net (code "58") (name "Net-(IC3-ROUT2)") (class "Default")
      (node (ref "IC3") (pin "6") (pinfunction "ROUT2_6") (pintype "output"))
      (node (ref "R23") (pin "2") (pinfunction "2_2") (pintype "passive"))
    )
    (net (code "59") (name "Net-(IC4-ROUT1)") (class "Default")
      (node (ref "IC4") (pin "7") (pinfunction "ROUT1_7") (pintype "output"))
      (node (ref "R31") (pin "2") (pinfunction "2_2") (pintype "passive"))
    )
    (net (code "60") (name "Net-(IC4-ROUT2)") (class "Default")
      (node (ref "IC4") (pin "6") (pinfunction "ROUT2_6") (pintype "output"))
      (node (ref "R35") (pin "2") (pinfunction "2_2") (pintype "passive"))
    )
    (net (code "61") (name "Net-(IC5-DIN1)") (class "Default")
      (node (ref "IC5") (pin "2") (pinfunction "DIN1_2") (pintype "input"))
      (node (ref "R36") (pin "2") (pinfunction "2_2") (pintype "passive"))
    )
    (net (code "62") (name "Net-(IC5-DIN2RIN-)") (class "Default")
      (node (ref "IC5") (pin "3") (pinfunction "DIN2RIN-_3") (pintype "input"))
      (node (ref "R83") (pin "2") (pinfunction "2_2") (pintype "passive"))
    )
    (net (code "63") (name "Net-(IC7-A0)") (class "Default")
      (node (ref "IC7") (pin "7") (pinfunction "A0_7") (pintype "input"))
      (node (ref "R48") (pin "2") (pinfunction "2_2") (pintype "passive"))
    )
    (net (code "64") (name "Net-(IC7-A1)") (class "Default")
      (node (ref "IC7") (pin "6") (pinfunction "A1_6") (pintype "input"))
      (node (ref "R47") (pin "2") (pinfunction "2_2") (pintype "passive"))
    )
    (net (code "65") (name "Net-(IC7-A2)") (class "Default")
      (node (ref "IC7") (pin "5") (pinfunction "A2_5") (pintype "input"))
      (node (ref "R46") (pin "2") (pinfunction "2_2") (pintype "passive"))
    )
    (net (code "66") (name "Net-(IC7-O.S.)") (class "Default")
      (node (ref "IC7") (pin "3") (pinfunction "O.S._3") (pintype "output"))
      (node (ref "LD1") (pin "1") (pinfunction "C_1") (pintype "passive"))
      (node (ref "R45") (pin "1") (pinfunction "1_1") (pintype "passive"))
    )
    (net (code "67") (name "Net-(LD1-A)") (class "Default")
      (node (ref "LD1") (pin "2") (pinfunction "A_2") (pintype "passive"))
      (node (ref "R106") (pin "1") (pinfunction "1_1") (pintype "passive"))
    )
    (net (code "68") (name "P3V3") (class "Default")
      (node (ref "C2") (pin "2") (pinfunction "2_2") (pintype "passive"))
      (node (ref "C3") (pin "2") (pinfunction "2_2") (pintype "passive"))
      (node (ref "C4") (pin "2") (pinfunction "2_2") (pintype "passive"))
      (node (ref "C5") (pin "2") (pinfunction "2_2") (pintype "passive"))
      (node (ref "IC2") (pin "8") (pinfunction "VCC_8") (pintype "power_in"))
      (node (ref "IC3") (pin "8") (pinfunction "VCC_8") (pintype "power_in"))
      (node (ref "IC4") (pin "8") (pinfunction "VCC_8") (pintype "power_in"))
      (node (ref "IC5") (pin "1") (pinfunction "VCC_1") (pintype "power_in"))
    )
    (net (code "69") (name "P3V3_MP") (class "Default")
      (node (ref "C6") (pin "2") (pinfunction "2_2") (pintype "passive"))
      (node (ref "C7") (pin "2") (pinfunction "2_2") (pintype "passive"))
      (node (ref "C8") (pin "2") (pinfunction "2_2") (pintype "passive"))
      (node (ref "D4") (pin "5") (pinfunction "VBUS_5") (pintype "power_in"))
      (node (ref "IC6") (pin "4") (pinfunction "VCC_4") (pintype "power_in"))
      (node (ref "IC7") (pin "8") (pinfunction "+VS_8") (pintype "power_in"))
      (node (ref "IC8") (pin "8") (pinfunction "VCC_8") (pintype "power_in"))
      (node (ref "J2") (pin "30") (pinfunction "30_30") (pintype "bidirectional"))
      (node (ref "R106") (pin "2") (pinfunction "2_2") (pintype "passive"))
      (node (ref "R40") (pin "2") (pinfunction "2_2") (pintype "passive"))
      (node (ref "R41") (pin "2") (pinfunction "2_2") (pintype "passive"))
      (node (ref "R42") (pin "1") (pinfunction "1_1") (pintype "passive"))
      (node (ref "R43") (pin "2") (pinfunction "2_2") (pintype "passive"))
      (node (ref "R44") (pin "2") (pinfunction "2_2") (pintype "passive"))
      (node (ref "TP3") (pin "1") (pinfunction "1_1") (pintype "bidirectional"))
    )
    (net (code "70") (name "P12V0") (class "Default")
      (node (ref "J2") (pin "28") (pinfunction "28_28") (pintype "bidirectional"))
      (node (ref "J2") (pin "29") (pinfunction "29_29") (pintype "bidirectional"))
      (node (ref "R37") (pin "1") (pinfunction "1_1") (pintype "passive"))
    )
    (net (code "71") (name "P12V0_CPCIS") (class "Default")
      (node (ref "R37") (pin "2") (pinfunction "2_2") (pintype "passive"))
    )
    (net (code "72") (name "unconnected-(D4-I{slash}O1-Pad1)") (class "Default")
      (node (ref "D4") (pin "1") (pinfunction "I/O1_1") (pintype "bidirectional+no_connect"))
    )
    (net (code "73") (name "unconnected-(D4-I{slash}O4-Pad6)") (class "Default")
      (node (ref "D4") (pin "6") (pinfunction "I/O4_6") (pintype "bidirectional+no_connect"))
    )
    (net (code "74") (name "unconnected-(IC6-NC-Pad5)") (class "Default")
      (node (ref "IC6") (pin "5") (pinfunction "NC_5") (pintype "passive+no_connect"))
    )
    (net (code "75") (name "unconnected-(IC8-NC-Pad7)") (class "Default")
      (node (ref "IC8") (pin "7") (pinfunction "NC_7") (pintype "passive+no_connect"))
    )
  )
)
